# Optocoupler-Isolation.net
KiCad netlist of a schematic drawn in Altium Designer
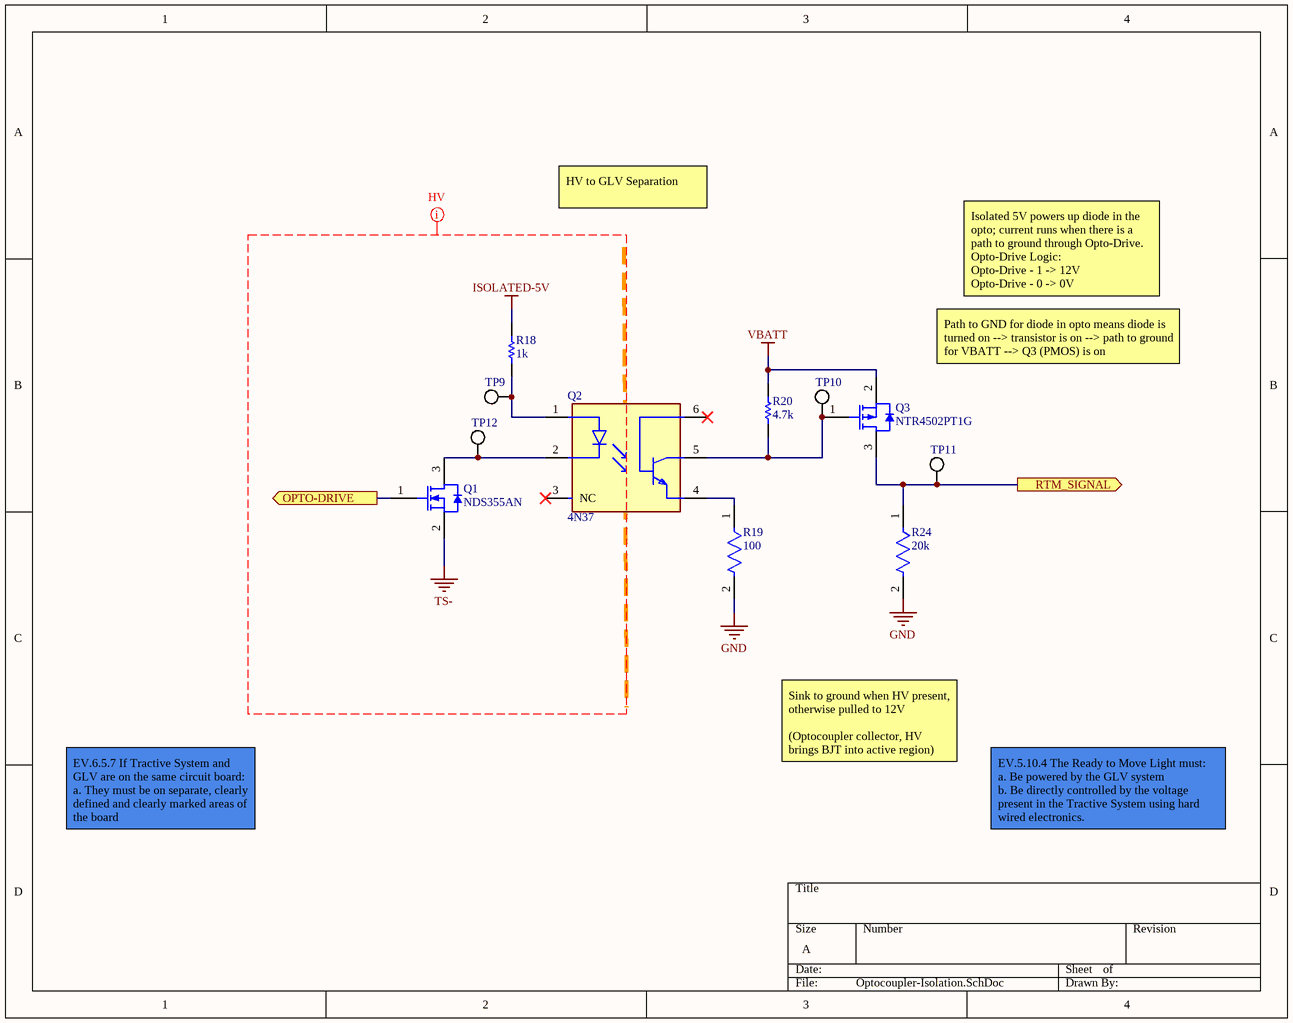
[diagram p0: Optocoupler-Isolation.SchDoc]

(export (version "E")
  (design (tool "Eeschema 10.0.6"))
  (components
    (comp (ref "Q1")
      (value "NDS355AN")
      (footprint "FAIR-SOT-3_V")
      (fields (field (name "MANUFACTURER") "FairchildSemiconductor"))
      (libsource (lib "Altium Content Vault") (part "NEMOS-GSD-3"))
    )
    (comp (ref "Q2")
      (value "4N37")
      (footprint "FP-4N37-MFG")
      (libsource (lib "Altium Content Vault") (part "cc3cd645612a37f745648d5741cac6e"))
    )
    (comp (ref "Q3")
      (value "NTR4502PT1G")
      (footprint "ONSC-SOT-23-3-318-08_V")
      (description "Power MOSFET, -30 V, -1.95 A, Single, P-Channel, 3-Pin SOT-23, Pb-Free, Tape and Reel")
      (fields (field (name "MANUFACTURER") "On Semiconductor"))
      (libsource (lib "Altium Content Vault") (part "ONSC-PMOS-G1S2D3-3_D"))
    )
    (comp (ref "R18")
      (value "1k")
      (footprint "RESC3225X70X50NL20T20")
      (description "360 Ohms ±1% 0.333W, 1/3W, FOOTPRINT-1210-GENERIC")
      (fields (field (name "PART NUMBER") "KTR25JZPF3600"))
      (libsource (lib "Altium Content Vault") (part "RES"))
    )
    (comp (ref "R19")
      (value "100")
      (footprint "FP-CRCW1206-e3-MFG")
      (description "RES Thick Film, 100Ω, 1%, 0.25W, 100ppm/°C, 1206")
      (fields (field (name "TOLERANCE") "1%"))
      (libsource (lib "Altium Content Vault") (part "1029c3af85768c4190bb7ad29bc67b5"))
    )
    (comp (ref "R20")
      (value "4.7k")
      (footprint "RESC3216X60X45ML15T20")
      (description "Chip Resistor, 4.7 KOhm, +/- 1%, 0.25 W, -55 to 155 degC, 1206 (3216 Metric), RoHS, Tape and Reel")
      (fields (field (name "MANUFACTURER") "Vishay Semiconductor") (field (name "TOLERANCE") "1%"))
      (libsource (lib "Altium Content Vault") (part "RES-2"))
    )
    (comp (ref "R24")
      (value "20k")
      (footprint "FP-CRCW1206-e3-MFG")
      (description "RES Thick Film, 20kΩ, 1%, 0.25W, 100ppm/°C, 1206")
      (fields (field (name "TOLERANCE") "1%"))
      (libsource (lib "Altium Content Vault") (part "1029c3af85768c4190bb7ad29bc67b5"))
    )
    (comp (ref "TP9")
      (value "~")
      (footprint "FOOTPRINT-GENERIC-TP-VIA-1MM")
      (libsource (lib "University of California Riverside - FSAE") (part "Misc-Generic-TP"))
    )
    (comp (ref "TP10")
      (value "~")
      (footprint "FOOTPRINT-GENERIC-TP-VIA-1MM")
      (libsource (lib "University of California Riverside - FSAE") (part "Misc-Generic-TP"))
    )
    (comp (ref "TP11")
      (value "~")
      (footprint "FOOTPRINT-GENERIC-TP-VIA-1MM")
      (libsource (lib "University of California Riverside - FSAE") (part "Misc-Generic-TP"))
    )
    (comp (ref "TP12")
      (value "~")
      (footprint "FOOTPRINT-GENERIC-TP-VIA-1MM")
      (libsource (lib "University of California Riverside - FSAE") (part "Misc-Generic-TP"))
    )
  )
  (nets
    (net (code "1") (name "/OPTO-DRIVE") (class "Default")
      (node (ref "Q1") (pin "1") (pinfunction "G_1") (pintype "passive"))
    )
    (net (code "2") (name "/RTM_SIGNAL") (class "Default")
      (node (ref "Q3") (pin "3") (pinfunction "D_3") (pintype "passive"))
      (node (ref "R24") (pin "1") (pinfunction "1_1") (pintype "passive"))
      (node (ref "TP11") (pin "1") (pinfunction "TP_1") (pintype "passive"))
    )
    (net (code "3") (name "GND") (class "Default")
      (node (ref "R19") (pin "2") (pinfunction "2_2") (pintype "passive"))
      (node (ref "R24") (pin "2") (pinfunction "2_2") (pintype "passive"))
    )
    (net (code "4") (name "ISOLATED-5V") (class "Default")
      (node (ref "R18") (pin "1") (pinfunction "1_1") (pintype "passive"))
    )
    (net (code "5") (name "Net-(Q1-D)") (class "Default")
      (node (ref "Q1") (pin "3") (pinfunction "D_3") (pintype "passive"))
      (node (ref "Q2") (pin "2") (pinfunction "C_2") (pintype "passive"))
      (node (ref "TP12") (pin "1") (pinfunction "TP_1") (pintype "passive"))
    )
    (net (code "6") (name "Net-(Q2-A)") (class "Default")
      (node (ref "Q2") (pin "1") (pinfunction "A_1") (pintype "passive"))
      (node (ref "R18") (pin "2") (pinfunction "2_2") (pintype "passive"))
      (node (ref "TP9") (pin "1") (pinfunction "TP_1") (pintype "passive"))
    )
    (net (code "7") (name "Net-(Q2-E)") (class "Default")
      (node (ref "Q2") (pin "4") (pinfunction "E_4") (pintype "passive"))
      (node (ref "R19") (pin "1") (pinfunction "1_1") (pintype "passive"))
    )
    (net (code "8") (name "Net-(Q3-G)") (class "Default")
      (node (ref "Q2") (pin "5") (pinfunction "C_5") (pintype "passive"))
      (node (ref "Q3") (pin "1") (pinfunction "G_1") (pintype "passive"))
      (node (ref "R20") (pin "1") (pinfunction "1_1") (pintype "passive"))
      (node (ref "TP10") (pin "1") (pinfunction "TP_1") (pintype "passive"))
    )
    (net (code "9") (name "TS-") (class "Default")
      (node (ref "Q1") (pin "2") (pinfunction "S_2") (pintype "passive"))
    )
    (net (code "10") (name "VBATT") (class "Default")
      (node (ref "Q3") (pin "2") (pinfunction "S_2") (pintype "passive"))
      (node (ref "R20") (pin "2") (pinfunction "2_2") (pintype "passive"))
    )
    (net (code "11") (name "unconnected-(Q2-B-Pad6)") (class "Default")
      (node (ref "Q2") (pin "6") (pinfunction "B_6") (pintype "passive+no_connect"))
    )
    (net (code "12") (name "unconnected-(Q2-NC-Pad3)") (class "Default")
      (node (ref "Q2") (pin "3") (pinfunction "NC_3") (pintype "passive+no_connect"))
    )
  )
)
